# WF_AutoCar.net
KiCad netlist of a schematic drawn in Altium Designer
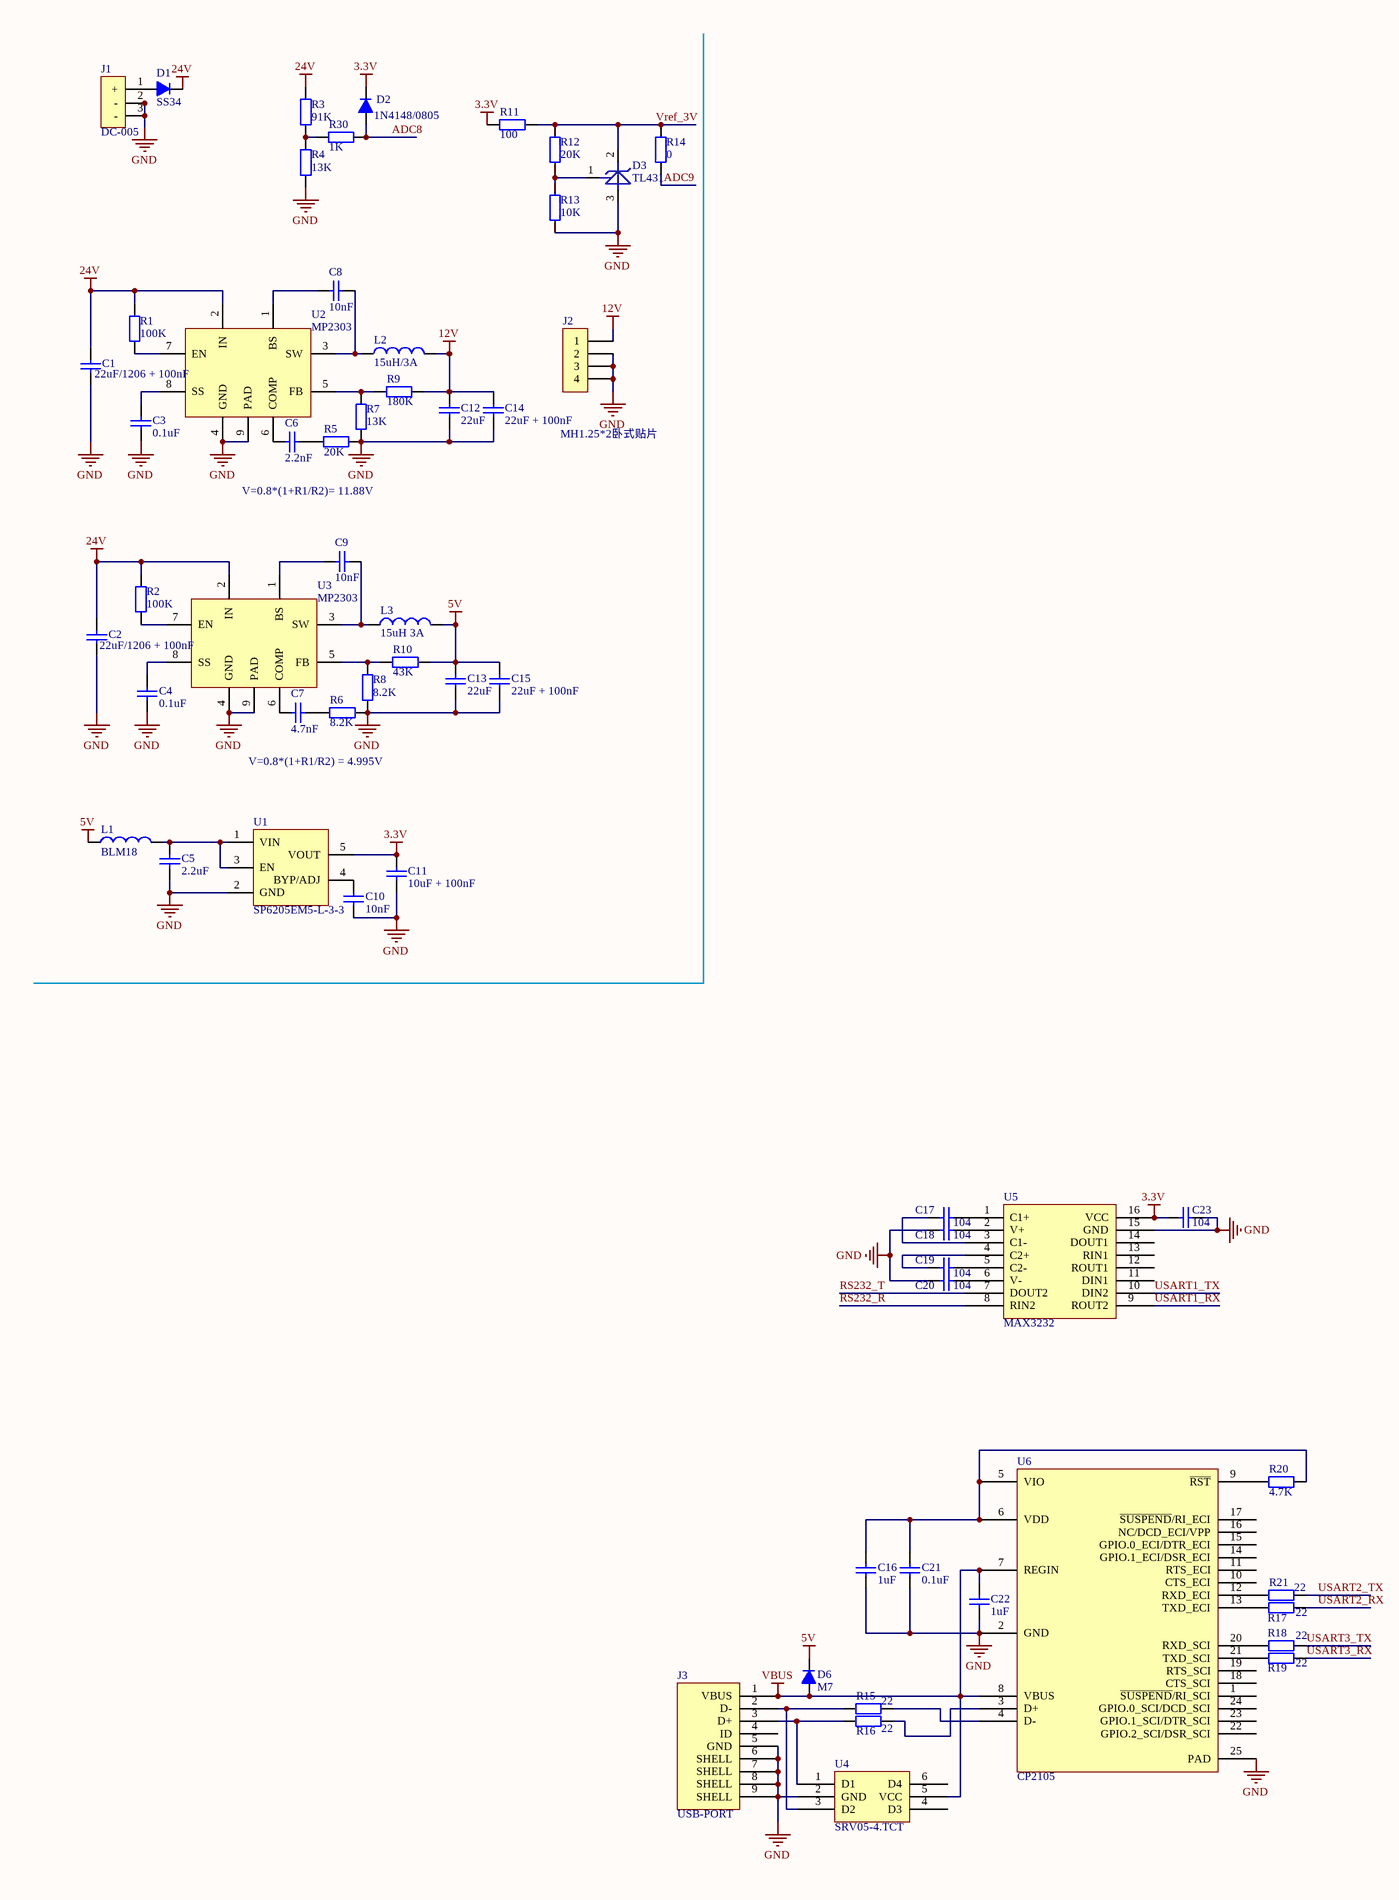
[diagram p0: WF_AutoCar.SchDoc, left]
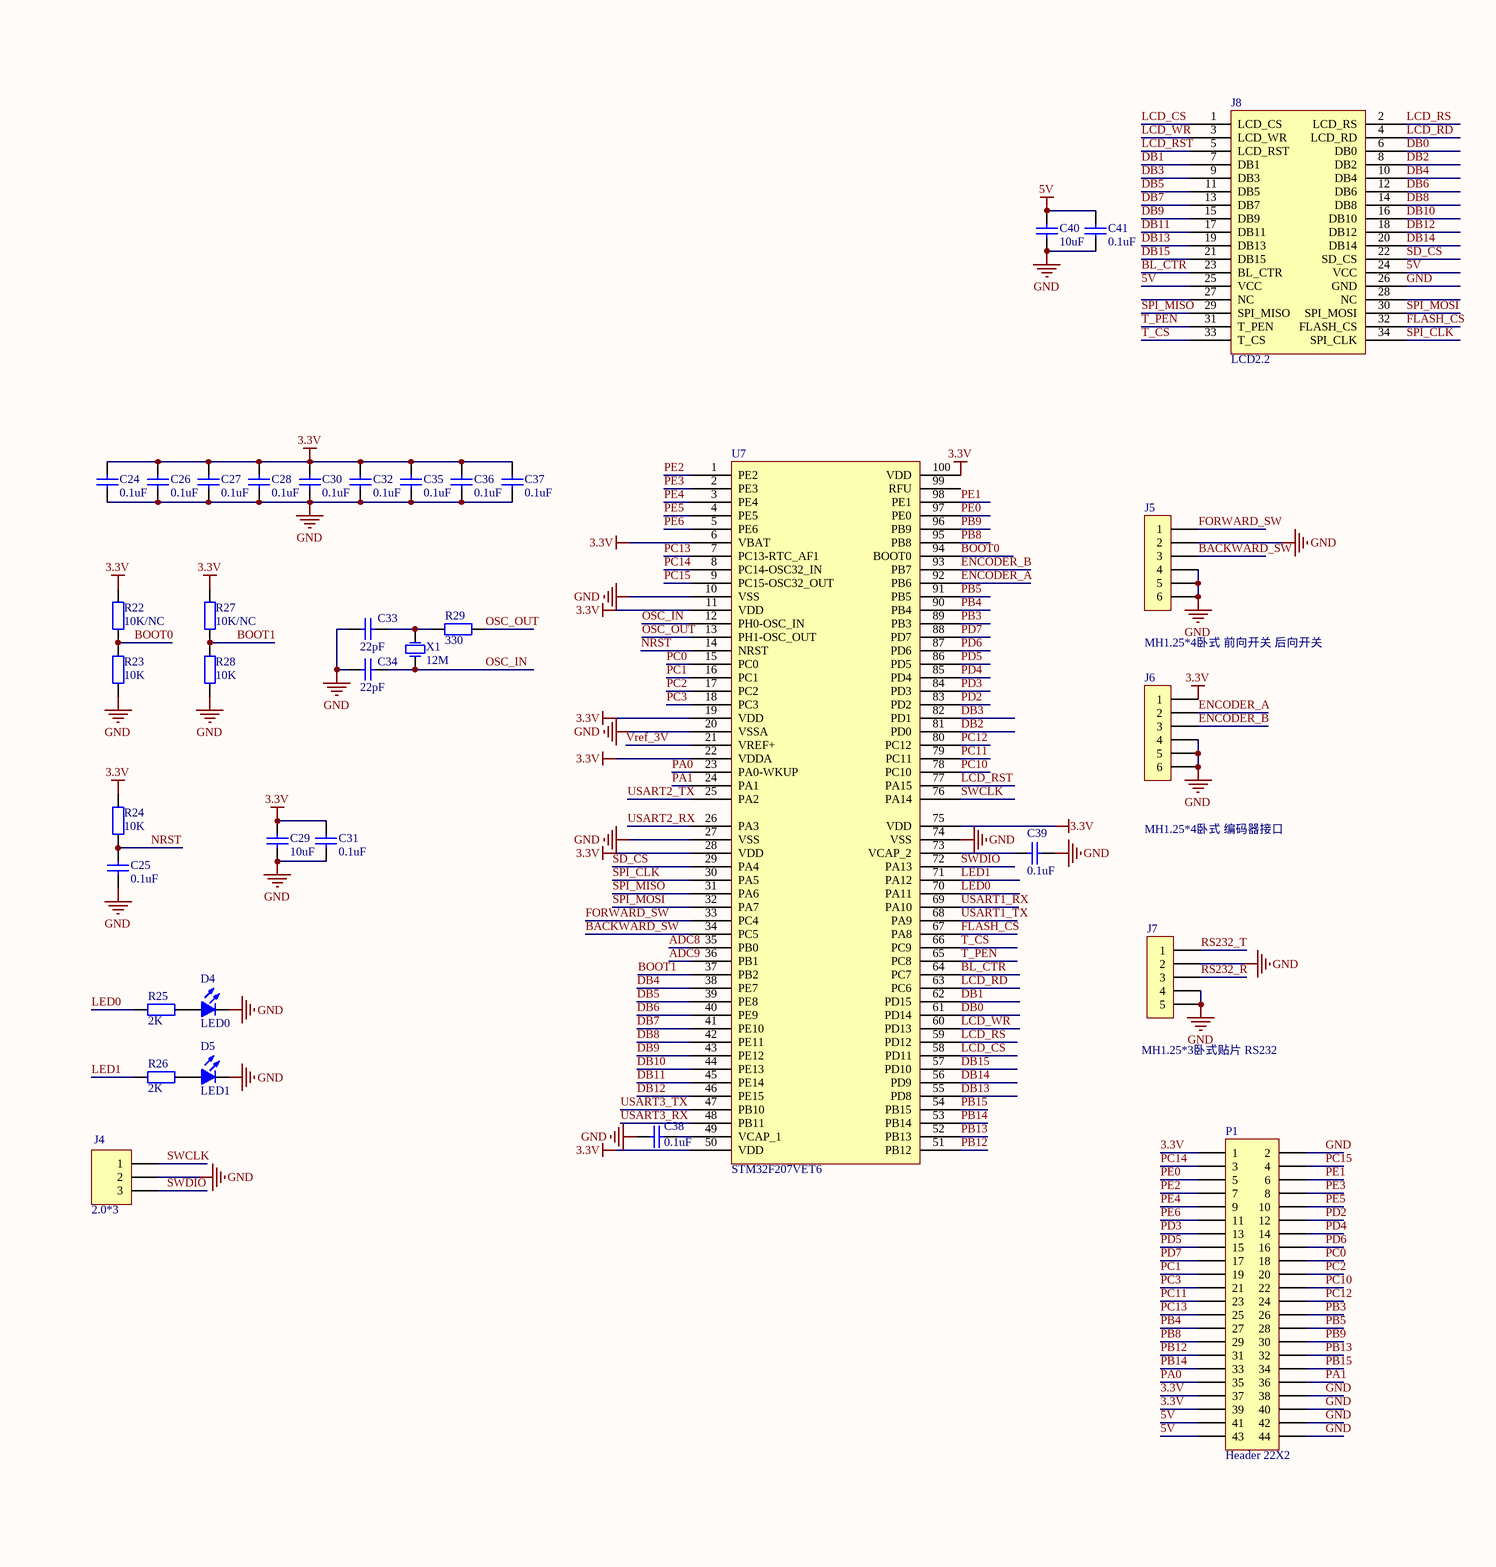
[diagram p1: WF_AutoCar.SchDoc, right]

(export (version "E")
  (design (tool "Eeschema 10.0.6"))
  (components
    (comp (ref "C1")
      (value "22uF/1206 + 100nF")
      (footprint "C1206")
      (description "Capacitor")
      (fields (field (name "Comment") "Cap1") (field (name "PUBLISHER") "Altium Limited"))
      (libsource (lib "weifengdq") (part "Cap1"))
    )
    (comp (ref "C2")
      (value "22uF/1206 + 100nF")
      (footprint "C1206")
      (description "Capacitor")
      (fields (field (name "Comment") "Cap1") (field (name "PUBLISHER") "Altium Limited"))
      (libsource (lib "weifengdq") (part "Cap1"))
    )
    (comp (ref "C3")
      (value "0.1uF")
      (footprint "C0402")
      (description "Capacitor")
      (fields (field (name "Comment") "Cap1") (field (name "PUBLISHER") "Altium Limited"))
      (libsource (lib "weifengdq") (part "Cap1"))
    )
    (comp (ref "C4")
      (value "0.1uF")
      (footprint "C0402")
      (description "Capacitor")
      (fields (field (name "Comment") "Cap1") (field (name "PUBLISHER") "Altium Limited"))
      (libsource (lib "weifengdq") (part "Cap1"))
    )
    (comp (ref "C5")
      (value "2.2uF")
      (footprint "CC0805")
      (description "Capacitor")
      (fields (field (name "Comment") "Cap1") (field (name "PUBLISHER") "Altium Limited"))
      (libsource (lib "weifengdq") (part "Cap1"))
    )
    (comp (ref "C6")
      (value "2.2nF")
      (footprint "C0402")
      (description "Capacitor")
      (fields (field (name "Comment") "Cap1") (field (name "PUBLISHER") "Altium Limited"))
      (libsource (lib "weifengdq") (part "Cap1"))
    )
    (comp (ref "C7")
      (value "4.7nF")
      (footprint "C0402")
      (description "Capacitor")
      (fields (field (name "Comment") "Cap1") (field (name "PUBLISHER") "Altium Limited"))
      (libsource (lib "weifengdq") (part "Cap1"))
    )
    (comp (ref "C8")
      (value "10nF")
      (footprint "C0402")
      (description "Capacitor")
      (fields (field (name "Comment") "Cap1") (field (name "PUBLISHER") "Altium Limited"))
      (libsource (lib "weifengdq") (part "Cap1"))
    )
    (comp (ref "C9")
      (value "10nF")
      (footprint "C0402")
      (description "Capacitor")
      (fields (field (name "Comment") "Cap1") (field (name "PUBLISHER") "Altium Limited"))
      (libsource (lib "weifengdq") (part "Cap1"))
    )
    (comp (ref "C10")
      (value "10nF")
      (footprint "C0402")
      (description "Capacitor")
      (fields (field (name "Comment") "Cap1") (field (name "PUBLISHER") "Altium Limited"))
      (libsource (lib "weifengdq") (part "Cap1"))
    )
    (comp (ref "C11")
      (value "10uF + 100nF")
      (footprint "CC0805")
      (description "Capacitor")
      (fields (field (name "Comment") "Cap1") (field (name "PUBLISHER") "Altium Limited"))
      (libsource (lib "weifengdq") (part "Cap1"))
    )
    (comp (ref "C12")
      (value "22uF")
      (footprint "CC0805")
      (description "Capacitor")
      (fields (field (name "Comment") "Cap1") (field (name "PUBLISHER") "Altium Limited"))
      (libsource (lib "weifengdq") (part "Cap1"))
    )
    (comp (ref "C13")
      (value "22uF")
      (footprint "CC0805")
      (description "Capacitor")
      (fields (field (name "Comment") "Cap1") (field (name "PUBLISHER") "Altium Limited"))
      (libsource (lib "weifengdq") (part "Cap1"))
    )
    (comp (ref "C14")
      (value "22uF + 100nF")
      (footprint "CC0805")
      (description "Capacitor")
      (fields (field (name "Comment") "Cap1") (field (name "PUBLISHER") "Altium Limited"))
      (libsource (lib "weifengdq") (part "Cap1"))
    )
    (comp (ref "C15")
      (value "22uF + 100nF")
      (footprint "CC0805")
      (description "Capacitor")
      (fields (field (name "Comment") "Cap1") (field (name "PUBLISHER") "Altium Limited"))
      (libsource (lib "weifengdq") (part "Cap1"))
    )
    (comp (ref "C16")
      (value "1uF")
      (footprint "C0402")
      (description "Capacitor")
      (fields (field (name "Comment") "Cap1") (field (name "PUBLISHER") "Altium Limited"))
      (libsource (lib "weifengdq") (part "Cap1"))
    )
    (comp (ref "C17")
      (value "104")
      (footprint "C0402")
      (description "Capacitor")
      (fields (field (name "Comment") "Cap1") (field (name "PUBLISHER") "Altium Limited"))
      (libsource (lib "weifengdq") (part "Cap1"))
    )
    (comp (ref "C18")
      (value "104")
      (footprint "C0402")
      (description "Capacitor")
      (fields (field (name "Comment") "Cap1") (field (name "PUBLISHER") "Altium Limited"))
      (libsource (lib "weifengdq") (part "Cap1"))
    )
    (comp (ref "C19")
      (value "104")
      (footprint "C0402")
      (description "Capacitor")
      (fields (field (name "Comment") "Cap1") (field (name "PUBLISHER") "Altium Limited"))
      (libsource (lib "weifengdq") (part "Cap1"))
    )
    (comp (ref "C20")
      (value "104")
      (footprint "C0402")
      (description "Capacitor")
      (fields (field (name "Comment") "Cap1") (field (name "PUBLISHER") "Altium Limited"))
      (libsource (lib "weifengdq") (part "Cap1"))
    )
    (comp (ref "C21")
      (value "0.1uF")
      (footprint "C0402")
      (description "Capacitor")
      (fields (field (name "Comment") "Cap1") (field (name "PUBLISHER") "Altium Limited"))
      (libsource (lib "weifengdq") (part "Cap1"))
    )
    (comp (ref "C22")
      (value "1uF")
      (footprint "C0402")
      (description "Capacitor")
      (fields (field (name "Comment") "Cap1") (field (name "PUBLISHER") "Altium Limited"))
      (libsource (lib "weifengdq") (part "Cap1"))
    )
    (comp (ref "C23")
      (value "104")
      (footprint "C0402")
      (description "Capacitor")
      (fields (field (name "Comment") "Cap1") (field (name "PUBLISHER") "Altium Limited"))
      (libsource (lib "weifengdq") (part "Cap1"))
    )
    (comp (ref "C24")
      (value "0.1uF")
      (footprint "C0402")
      (description "Capacitor")
      (fields (field (name "Comment") "Cap1") (field (name "PUBLISHER") "Altium Limited"))
      (libsource (lib "weifengdq") (part "Cap1"))
    )
    (comp (ref "C25")
      (value "0.1uF")
      (footprint "C0402")
      (description "Capacitor")
      (fields (field (name "Comment") "Cap1") (field (name "PUBLISHER") "Altium Limited"))
      (libsource (lib "weifengdq") (part "Cap1"))
    )
    (comp (ref "C26")
      (value "0.1uF")
      (footprint "C0402")
      (description "Capacitor")
      (fields (field (name "Comment") "Cap1") (field (name "PUBLISHER") "Altium Limited"))
      (libsource (lib "weifengdq") (part "Cap1"))
    )
    (comp (ref "C27")
      (value "0.1uF")
      (footprint "C0402")
      (description "Capacitor")
      (fields (field (name "Comment") "Cap1") (field (name "PUBLISHER") "Altium Limited"))
      (libsource (lib "weifengdq") (part "Cap1"))
    )
    (comp (ref "C28")
      (value "0.1uF")
      (footprint "C0402")
      (description "Capacitor")
      (fields (field (name "Comment") "Cap1") (field (name "PUBLISHER") "Altium Limited"))
      (libsource (lib "weifengdq") (part "Cap1"))
    )
    (comp (ref "C29")
      (value "10uF")
      (footprint "CC0805")
      (description "Capacitor")
      (fields (field (name "Comment") "Cap1") (field (name "PUBLISHER") "Altium Limited"))
      (libsource (lib "weifengdq") (part "Cap1"))
    )
    (comp (ref "C30")
      (value "0.1uF")
      (footprint "C0402")
      (description "Capacitor")
      (fields (field (name "Comment") "Cap1") (field (name "PUBLISHER") "Altium Limited"))
      (libsource (lib "weifengdq") (part "Cap1"))
    )
    (comp (ref "C31")
      (value "0.1uF")
      (footprint "C0402")
      (description "Capacitor")
      (fields (field (name "Comment") "Cap1") (field (name "PUBLISHER") "Altium Limited"))
      (libsource (lib "weifengdq") (part "Cap1"))
    )
    (comp (ref "C32")
      (value "0.1uF")
      (footprint "C0402")
      (description "Capacitor")
      (fields (field (name "Comment") "Cap1") (field (name "PUBLISHER") "Altium Limited"))
      (libsource (lib "weifengdq") (part "Cap1"))
    )
    (comp (ref "C33")
      (value "22pF")
      (footprint "C0402")
      (description "Capacitor")
      (fields (field (name "Comment") "Cap1") (field (name "PUBLISHER") "Altium Limited"))
      (libsource (lib "weifengdq") (part "Cap1"))
    )
    (comp (ref "C34")
      (value "22pF")
      (footprint "C0402")
      (description "Capacitor")
      (fields (field (name "Comment") "Cap1") (field (name "PUBLISHER") "Altium Limited"))
      (libsource (lib "weifengdq") (part "Cap1"))
    )
    (comp (ref "C35")
      (value "0.1uF")
      (footprint "C0402")
      (description "Capacitor")
      (fields (field (name "Comment") "Cap1") (field (name "PUBLISHER") "Altium Limited"))
      (libsource (lib "weifengdq") (part "Cap1"))
    )
    (comp (ref "C36")
      (value "0.1uF")
      (footprint "C0402")
      (description "Capacitor")
      (fields (field (name "Comment") "Cap1") (field (name "PUBLISHER") "Altium Limited"))
      (libsource (lib "weifengdq") (part "Cap1"))
    )
    (comp (ref "C37")
      (value "0.1uF")
      (footprint "C0402")
      (description "Capacitor")
      (fields (field (name "Comment") "Cap1") (field (name "PUBLISHER") "Altium Limited"))
      (libsource (lib "weifengdq") (part "Cap1"))
    )
    (comp (ref "C38")
      (value "0.1uF")
      (footprint "C0402")
      (description "Capacitor")
      (fields (field (name "Comment") "Cap1") (field (name "PUBLISHER") "Altium Limited"))
      (libsource (lib "weifengdq") (part "Cap1"))
    )
    (comp (ref "C39")
      (value "0.1uF")
      (footprint "C0402")
      (description "Capacitor")
      (fields (field (name "Comment") "Cap1") (field (name "PUBLISHER") "Altium Limited"))
      (libsource (lib "weifengdq") (part "Cap1"))
    )
    (comp (ref "C40")
      (value "10uF")
      (footprint "CC0805")
      (description "Capacitor")
      (fields (field (name "Comment") "Cap1") (field (name "PUBLISHER") "Altium Limited"))
      (libsource (lib "weifengdq") (part "Cap1"))
    )
    (comp (ref "C41")
      (value "0.1uF")
      (footprint "C0402")
      (description "Capacitor")
      (fields (field (name "Comment") "Cap1") (field (name "PUBLISHER") "Altium Limited"))
      (libsource (lib "weifengdq") (part "Cap1"))
    )
    (comp (ref "D1")
      (value "SS34")
      (footprint "LC-SMA(DO-214AC)_S2")
      (libsource (lib "weifengdq") (part "Diode1"))
    )
    (comp (ref "D2")
      (value "1N4148/0805")
      (footprint "Diode-0805")
      (libsource (lib "weifengdq") (part "Diode1"))
    )
    (comp (ref "D3") (value "TL431") (footprint "SOT-23") (libsource (lib "weifengdq") (part "TL431-SOT23")))
    (comp (ref "D4")
      (value "LED0")
      (footprint "DIODE-12")
      (description "Typical INFRARED GaAs LED")
      (fields (field (name "PUBLISHER") "Altium Limited"))
      (libsource (lib "weifengdq") (part "LED1"))
    )
    (comp (ref "D5")
      (value "LED1")
      (footprint "DIODE-12")
      (description "Typical INFRARED GaAs LED")
      (fields (field (name "PUBLISHER") "Altium Limited"))
      (libsource (lib "weifengdq") (part "LED1"))
    )
    (comp (ref "D6")
      (value "M7")
      (footprint "LC-SMA(DO-214AC)_S2")
      (libsource (lib "weifengdq") (part "Diode1"))
    )
    (comp (ref "J1") (value "DC-005") (footprint "DC10B") (libsource (lib "weifengdq") (part "DC-005")))
    (comp (ref "J2")
      (value "MH1.25*2卧式贴片")
      (footprint "MH1.25*2立式表贴")
      (libsource (lib "weifengdq") (part "MH1.25*2卧式贴片"))
    )
    (comp (ref "J3")
      (value "USB-PORT")
      (footprint "USB/SM0.8-6H5")
      (libsource (lib "weifengdq") (part "USB-PORT"))
    )
    (comp (ref "J4")
      (value "2.0*3")
      (footprint "Con3_2.0")
      (description "Header, 3-Pin")
      (fields (field (name "PUBLISHER") "Altium Limited"))
      (libsource (lib "weifengdq") (part "Con3_2.0"))
    )
    (comp (ref "J5")
      (value "MH1.25*4卧式 前向开关 后向开关")
      (footprint "MH1.25*4立式表贴")
      (libsource (lib "weifengdq") (part "MH1.25*4立式贴片"))
    )
    (comp (ref "J6")
      (value "MH1.25*4卧式 编码器接口")
      (footprint "MH1.25*4立式表贴")
      (libsource (lib "weifengdq") (part "MH1.25*4立式贴片"))
    )
    (comp (ref "J7")
      (value "MH1.25*3卧式贴片 RS232")
      (footprint "MH1.25*3立式表贴")
      (libsource (lib "weifengdq") (part "MH1.25*3卧式贴片"))
    )
    (comp (ref "J8")
      (value "LCD2.2")
      (footprint "2.2TFT_ILI9325")
      (libsource (lib "weifengdq") (part "2.2 LCD ILI9325"))
    )
    (comp (ref "L1") (value "BLM18") (footprint "CC0805") (libsource (lib "weifengdq") (part "BLM18")))
    (comp (ref "L2")
      (value "15uH/3A")
      (footprint "0630")
      (description "Inductor")
      (fields (field (name "PUBLISHER") "Altium Limited"))
      (libsource (lib "weifengdq") (part "Inductor"))
    )
    (comp (ref "L3")
      (value "15uH 3A")
      (footprint "0630")
      (description "Inductor")
      (fields (field (name "PUBLISHER") "Altium Limited"))
      (libsource (lib "weifengdq") (part "Inductor"))
    )
    (comp (ref "P1")
      (value "Header 22X2")
      (footprint "HDR2X22")
      (description "Header, 22-Pin, Dual row")
      (fields (field (name "PUBLISHER") "Altium Limited"))
      (libsource (lib "Miscellaneous Connectors") (part "Header 22X2"))
    )
    (comp (ref "R1")
      (value "100K")
      (footprint "C0402")
      (description "Resistor")
      (fields (field (name "Comment") "Res1") (field (name "PUBLISHER") "Altium Limited"))
      (libsource (lib "weifengdq") (part "Res1"))
    )
    (comp (ref "R2")
      (value "100K")
      (footprint "C0402")
      (description "Resistor")
      (fields (field (name "Comment") "Res1") (field (name "PUBLISHER") "Altium Limited"))
      (libsource (lib "weifengdq") (part "Res1"))
    )
    (comp (ref "R3")
      (value "91K")
      (footprint "C0402")
      (description "Resistor")
      (fields (field (name "Comment") "Res1") (field (name "PUBLISHER") "Altium Limited"))
      (libsource (lib "weifengdq") (part "Res1"))
    )
    (comp (ref "R4")
      (value "13K")
      (footprint "C0402")
      (description "Resistor")
      (fields (field (name "Comment") "Res1") (field (name "PUBLISHER") "Altium Limited"))
      (libsource (lib "weifengdq") (part "Res1"))
    )
    (comp (ref "R5")
      (value "20K")
      (footprint "C0402")
      (description "Resistor")
      (fields (field (name "Comment") "Res1") (field (name "PUBLISHER") "Altium Limited"))
      (libsource (lib "") (part "Res1_1"))
    )
    (comp (ref "R6")
      (value "8.2K")
      (footprint "C0402")
      (description "Resistor")
      (fields (field (name "Comment") "Res1") (field (name "PUBLISHER") "Altium Limited"))
      (libsource (lib "") (part "Res1_1"))
    )
    (comp (ref "R7")
      (value "13K")
      (footprint "C0402")
      (description "Resistor")
      (fields (field (name "Comment") "Res1") (field (name "PUBLISHER") "Altium Limited"))
      (libsource (lib "weifengdq") (part "Res1"))
    )
    (comp (ref "R8")
      (value "8.2K")
      (footprint "C0402")
      (description "Resistor")
      (fields (field (name "Comment") "Res1") (field (name "PUBLISHER") "Altium Limited"))
      (libsource (lib "weifengdq") (part "Res1"))
    )
    (comp (ref "R9")
      (value "180K")
      (footprint "C0402")
      (description "Resistor")
      (fields (field (name "Comment") "Res1") (field (name "PUBLISHER") "Altium Limited"))
      (libsource (lib "") (part "Res1_1"))
    )
    (comp (ref "R10")
      (value "43K")
      (footprint "C0402")
      (description "Resistor")
      (fields (field (name "Comment") "Res1") (field (name "PUBLISHER") "Altium Limited"))
      (libsource (lib "") (part "Res1_1"))
    )
    (comp (ref "R11")
      (value "100")
      (footprint "C0402")
      (description "Resistor")
      (fields (field (name "Comment") "Res1") (field (name "PUBLISHER") "Altium Limited"))
      (libsource (lib "") (part "Res1_2"))
    )
    (comp (ref "R12")
      (value "20K")
      (footprint "C0402")
      (description "Resistor")
      (fields (field (name "Comment") "Res1") (field (name "PUBLISHER") "Altium Limited"))
      (libsource (lib "") (part "Res1_3"))
    )
    (comp (ref "R13")
      (value "10K")
      (footprint "C0402")
      (description "Resistor")
      (fields (field (name "Comment") "Res1") (field (name "PUBLISHER") "Altium Limited"))
      (libsource (lib "") (part "Res1_3"))
    )
    (comp (ref "R14")
      (value "0")
      (footprint "C0402")
      (description "Resistor")
      (fields (field (name "Comment") "Res1") (field (name "PUBLISHER") "Altium Limited"))
      (libsource (lib "weifengdq") (part "Res1"))
    )
    (comp (ref "R15")
      (value "22")
      (footprint "C0402")
      (description "Resistor")
      (fields (field (name "Comment") "Res1") (field (name "PUBLISHER") "Altium Limited"))
      (libsource (lib "") (part "Res1_1"))
    )
    (comp (ref "R16")
      (value "22")
      (footprint "C0402")
      (description "Resistor")
      (fields (field (name "Comment") "Res1") (field (name "PUBLISHER") "Altium Limited"))
      (libsource (lib "") (part "Res1_1"))
    )
    (comp (ref "R17")
      (value "22")
      (footprint "C0402")
      (description "Resistor")
      (fields (field (name "Comment") "Res1") (field (name "PUBLISHER") "Altium Limited"))
      (libsource (lib "") (part "Res1_1"))
    )
    (comp (ref "R18")
      (value "22")
      (footprint "C0402")
      (description "Resistor")
      (fields (field (name "Comment") "Res1") (field (name "PUBLISHER") "Altium Limited"))
      (libsource (lib "") (part "Res1_1"))
    )
    (comp (ref "R19")
      (value "22")
      (footprint "C0402")
      (description "Resistor")
      (fields (field (name "Comment") "Res1") (field (name "PUBLISHER") "Altium Limited"))
      (libsource (lib "") (part "Res1_1"))
    )
    (comp (ref "R20")
      (value "4.7K")
      (footprint "C0402")
      (description "Resistor")
      (fields (field (name "Comment") "Res1") (field (name "PUBLISHER") "Altium Limited"))
      (libsource (lib "") (part "Res1_1"))
    )
    (comp (ref "R21")
      (value "22")
      (footprint "C0402")
      (description "Resistor")
      (fields (field (name "Comment") "Res1") (field (name "PUBLISHER") "Altium Limited"))
      (libsource (lib "") (part "Res1_1"))
    )
    (comp (ref "R22")
      (value "10K/NC")
      (footprint "C0402")
      (description "Resistor")
      (fields (field (name "Comment") "Res1") (field (name "PUBLISHER") "Altium Limited"))
      (libsource (lib "weifengdq") (part "Res1"))
    )
    (comp (ref "R23")
      (value "10K")
      (footprint "C0402")
      (description "Resistor")
      (fields (field (name "Comment") "Res1") (field (name "PUBLISHER") "Altium Limited"))
      (libsource (lib "weifengdq") (part "Res1"))
    )
    (comp (ref "R24")
      (value "10K")
      (footprint "C0402")
      (description "Resistor")
      (fields (field (name "Comment") "Res1") (field (name "PUBLISHER") "Altium Limited"))
      (libsource (lib "") (part "Res1_3"))
    )
    (comp (ref "R25")
      (value "2K")
      (footprint "C0402")
      (description "Resistor")
      (fields (field (name "Comment") "Res1") (field (name "PUBLISHER") "Altium Limited"))
      (libsource (lib "") (part "Res1_1"))
    )
    (comp (ref "R26")
      (value "2K")
      (footprint "C0402")
      (description "Resistor")
      (fields (field (name "Comment") "Res1") (field (name "PUBLISHER") "Altium Limited"))
      (libsource (lib "") (part "Res1_1"))
    )
    (comp (ref "R27")
      (value "10K/NC")
      (footprint "C0402")
      (description "Resistor")
      (fields (field (name "Comment") "Res1") (field (name "PUBLISHER") "Altium Limited"))
      (libsource (lib "weifengdq") (part "Res1"))
    )
    (comp (ref "R28")
      (value "10K")
      (footprint "C0402")
      (description "Resistor")
      (fields (field (name "Comment") "Res1") (field (name "PUBLISHER") "Altium Limited"))
      (libsource (lib "weifengdq") (part "Res1"))
    )
    (comp (ref "R29")
      (value "330")
      (footprint "C0402")
      (description "Resistor")
      (fields (field (name "Comment") "Res1") (field (name "PUBLISHER") "Altium Limited"))
      (libsource (lib "") (part "Res1_2"))
    )
    (comp (ref "R30")
      (value "1K")
      (footprint "C0402")
      (description "Resistor")
      (fields (field (name "Comment") "Res1") (field (name "PUBLISHER") "Altium Limited"))
      (libsource (lib "") (part "Res1_1"))
    )
    (comp (ref "U1")
      (value "SP6205EM5-L-3-3")
      (footprint "LC-SOT-23-5")
      (libsource (lib "weifengdq") (part "SP6205EM5-L-3-3"))
    )
    (comp (ref "U2")
      (value "MP2303")
      (footprint "LC-SOIC-8_150mil")
      (libsource (lib "weifengdq") (part "MP2307"))
    )
    (comp (ref "U3")
      (value "MP2303")
      (footprint "LC-SOIC-8_150mil")
      (libsource (lib "weifengdq") (part "MP2307"))
    )
    (comp (ref "U4")
      (value "SRV05-4.TCT")
      (footprint "LC-SOT-23-6")
      (libsource (lib "weifengdq") (part "SRV05-4.TCT"))
    )
    (comp (ref "U5") (value "MAX3232") (footprint "SOP16M") (libsource (lib "weifengdq") (part "MAX3232")))
    (comp (ref "U6") (value "CP2105") (footprint "QFN-24") (libsource (lib "weifengdq") (part "CP2105")))
    (comp (ref "U7")
      (value "STM32F207VET6")
      (footprint "LC-LQFP-100_14x14x05P")
      (libsource (lib "weifengdq") (part "STM32F207VET6"))
    )
    (comp (ref "X1")
      (value "12M")
      (footprint "XTAL-3225")
      (description "Crystal Oscillator")
      (fields (field (name "PUBLISHER") "Altium Limited"))
      (libsource (lib "weifengdq") (part "XTAL_1"))
    )
  )
  (nets
    (net (code "1") (name "/ADC8") (class "Default")
      (node (ref "D2") (pin "1") (pinfunction "A_1") (pintype "passive"))
      (node (ref "R30") (pin "2") (pinfunction "2_2") (pintype "passive"))
      (node (ref "U7") (pin "35") (pinfunction "PB0_35") (pintype "passive"))
    )
    (net (code "2") (name "/ADC9") (class "Default")
      (node (ref "R14") (pin "1") (pinfunction "1_1") (pintype "passive"))
      (node (ref "U7") (pin "36") (pinfunction "PB1_36") (pintype "passive"))
    )
    (net (code "3") (name "/BACKWARD_SW") (class "Default")
      (node (ref "J5") (pin "3") (pinfunction "3_3") (pintype "passive"))
      (node (ref "U7") (pin "34") (pinfunction "PC5_34") (pintype "passive"))
    )
    (net (code "4") (name "/BL_CTR") (class "Default")
      (node (ref "J8") (pin "23") (pinfunction "BL_CTR_23") (pintype "passive"))
      (node (ref "U7") (pin "64") (pinfunction "PC7_64") (pintype "passive"))
    )
    (net (code "5") (name "/BOOT0") (class "Default")
      (node (ref "R22") (pin "1") (pinfunction "1_1") (pintype "passive"))
      (node (ref "R23") (pin "2") (pinfunction "2_2") (pintype "passive"))
      (node (ref "U7") (pin "94") (pinfunction "BOOT0_94") (pintype "passive"))
    )
    (net (code "6") (name "/BOOT1") (class "Default")
      (node (ref "R27") (pin "1") (pinfunction "1_1") (pintype "passive"))
      (node (ref "R28") (pin "2") (pinfunction "2_2") (pintype "passive"))
      (node (ref "U7") (pin "37") (pinfunction "PB2_37") (pintype "passive"))
    )
    (net (code "7") (name "/DB0") (class "Default")
      (node (ref "J8") (pin "6") (pinfunction "DB0_6") (pintype "passive"))
      (node (ref "U7") (pin "61") (pinfunction "PD14_61") (pintype "passive"))
    )
    (net (code "8") (name "/DB1") (class "Default")
      (node (ref "J8") (pin "7") (pinfunction "DB1_7") (pintype "passive"))
      (node (ref "U7") (pin "62") (pinfunction "PD15_62") (pintype "passive"))
    )
    (net (code "9") (name "/DB2") (class "Default")
      (node (ref "J8") (pin "8") (pinfunction "DB2_8") (pintype "passive"))
      (node (ref "U7") (pin "81") (pinfunction "PD0_81") (pintype "passive"))
    )
    (net (code "10") (name "/DB3") (class "Default")
      (node (ref "J8") (pin "9") (pinfunction "DB3_9") (pintype "passive"))
      (node (ref "U7") (pin "82") (pinfunction "PD1_82") (pintype "passive"))
    )
    (net (code "11") (name "/DB4") (class "Default")
      (node (ref "J8") (pin "10") (pinfunction "DB4_10") (pintype "passive"))
      (node (ref "U7") (pin "38") (pinfunction "PE7_38") (pintype "passive"))
    )
    (net (code "12") (name "/DB5") (class "Default")
      (node (ref "J8") (pin "11") (pinfunction "DB5_11") (pintype "passive"))
      (node (ref "U7") (pin "39") (pinfunction "PE8_39") (pintype "passive"))
    )
    (net (code "13") (name "/DB6") (class "Default")
      (node (ref "J8") (pin "12") (pinfunction "DB6_12") (pintype "passive"))
      (node (ref "U7") (pin "40") (pinfunction "PE9_40") (pintype "passive"))
    )
    (net (code "14") (name "/DB7") (class "Default")
      (node (ref "J8") (pin "13") (pinfunction "DB7_13") (pintype "passive"))
      (node (ref "U7") (pin "41") (pinfunction "PE10_41") (pintype "passive"))
    )
    (net (code "15") (name "/DB8") (class "Default")
      (node (ref "J8") (pin "14") (pinfunction "DB8_14") (pintype "passive"))
      (node (ref "U7") (pin "42") (pinfunction "PE11_42") (pintype "passive"))
    )
    (net (code "16") (name "/DB9") (class "Default")
      (node (ref "J8") (pin "15") (pinfunction "DB9_15") (pintype "passive"))
      (node (ref "U7") (pin "43") (pinfunction "PE12_43") (pintype "passive"))
    )
    (net (code "17") (name "/DB10") (class "Default")
      (node (ref "J8") (pin "16") (pinfunction "DB10_16") (pintype "passive"))
      (node (ref "U7") (pin "44") (pinfunction "PE13_44") (pintype "passive"))
    )
    (net (code "18") (name "/DB11") (class "Default")
      (node (ref "J8") (pin "17") (pinfunction "DB11_17") (pintype "passive"))
      (node (ref "U7") (pin "45") (pinfunction "PE14_45") (pintype "passive"))
    )
    (net (code "19") (name "/DB12") (class "Default")
      (node (ref "J8") (pin "18") (pinfunction "DB12_18") (pintype "passive"))
      (node (ref "U7") (pin "46") (pinfunction "PE15_46") (pintype "passive"))
    )
    (net (code "20") (name "/DB13") (class "Default")
      (node (ref "J8") (pin "19") (pinfunction "DB13_19") (pintype "passive"))
      (node (ref "U7") (pin "55") (pinfunction "PD8_55") (pintype "passive"))
    )
    (net (code "21") (name "/DB14") (class "Default")
      (node (ref "J8") (pin "20") (pinfunction "DB14_20") (pintype "passive"))
      (node (ref "U7") (pin "56") (pinfunction "PD9_56") (pintype "passive"))
    )
    (net (code "22") (name "/DB15") (class "Default")
      (node (ref "J8") (pin "21") (pinfunction "DB15_21") (pintype "passive"))
      (node (ref "U7") (pin "57") (pinfunction "PD10_57") (pintype "passive"))
    )
    (net (code "23") (name "/ENCODER_A") (class "Default")
      (node (ref "J6") (pin "2") (pinfunction "2_2") (pintype "passive"))
      (node (ref "U7") (pin "92") (pinfunction "PB6_92") (pintype "passive"))
    )
    (net (code "24") (name "/ENCODER_B") (class "Default")
      (node (ref "J6") (pin "3") (pinfunction "3_3") (pintype "passive"))
      (node (ref "U7") (pin "93") (pinfunction "PB7_93") (pintype "passive"))
    )
    (net (code "25") (name "/FLASH_CS") (class "Default")
      (node (ref "J8") (pin "32") (pinfunction "FLASH_CS_32") (pintype "passive"))
      (node (ref "U7") (pin "67") (pinfunction "PA8_67") (pintype "passive"))
    )
    (net (code "26") (name "/FORWARD_SW") (class "Default")
      (node (ref "J5") (pin "1") (pinfunction "1_1") (pintype "passive"))
      (node (ref "U7") (pin "33") (pinfunction "PC4_33") (pintype "passive"))
    )
    (net (code "27") (name "/LCD_CS") (class "Default")
      (node (ref "J8") (pin "1") (pinfunction "LCD_CS_1") (pintype "passive"))
      (node (ref "U7") (pin "58") (pinfunction "PD11_58") (pintype "passive"))
    )
    (net (code "28") (name "/LCD_RD") (class "Default")
      (node (ref "J8") (pin "4") (pinfunction "LCD_RD_4") (pintype "passive"))
      (node (ref "U7") (pin "63") (pinfunction "PC6_63") (pintype "passive"))
    )
    (net (code "29") (name "/LCD_RS") (class "Default")
      (node (ref "J8") (pin "2") (pinfunction "LCD_RS_2") (pintype "passive"))
      (node (ref "U7") (pin "59") (pinfunction "PD12_59") (pintype "passive"))
    )
    (net (code "30") (name "/LCD_RST") (class "Default")
      (node (ref "J8") (pin "5") (pinfunction "LCD_RST_5") (pintype "passive"))
      (node (ref "U7") (pin "77") (pinfunction "PA15_77") (pintype "passive"))
    )
    (net (code "31") (name "/LCD_WR") (class "Default")
      (node (ref "J8") (pin "3") (pinfunction "LCD_WR_3") (pintype "passive"))
      (node (ref "U7") (pin "60") (pinfunction "PD13_60") (pintype "passive"))
    )
    (net (code "32") (name "/LED0") (class "Default")
      (node (ref "R25") (pin "1") (pinfunction "1_1") (pintype "passive"))
      (node (ref "U7") (pin "70") (pinfunction "PA11_70") (pintype "passive"))
    )
    (net (code "33") (name "/LED1") (class "Default")
      (node (ref "R26") (pin "1") (pinfunction "1_1") (pintype "passive"))
      (node (ref "U7") (pin "71") (pinfunction "PA12_71") (pintype "passive"))
    )
    (net (code "34") (name "/NRST") (class "Default")
      (node (ref "C25") (pin "2") (pinfunction "2_2") (pintype "passive"))
      (node (ref "R24") (pin "2") (pinfunction "2_2") (pintype "passive"))
      (node (ref "U7") (pin "14") (pinfunction "NRST_14") (pintype "passive"))
    )
    (net (code "35") (name "/OSC_IN") (class "Default")
      (node (ref "C34") (pin "1") (pinfunction "1_1") (pintype "passive"))
      (node (ref "U7") (pin "12") (pinfunction "PH0-OSC_IN_12") (pintype "passive"))
      (node (ref "X1") (pin "2") (pinfunction "OSC2_2") (pintype "passive"))
    )
    (net (code "36") (name "/OSC_OUT") (class "Default")
      (node (ref "R29") (pin "1") (pinfunction "1_1") (pintype "passive"))
      (node (ref "U7") (pin "13") (pinfunction "PH1-OSC_OUT_13") (pintype "passive"))
    )
    (net (code "37") (name "/PA0") (class "Default")
      (node (ref "P1") (pin "35") (pinfunction "35_35") (pintype "passive"))
      (node (ref "U7") (pin "23") (pinfunction "PA0-WKUP_23") (pintype "passive"))
    )
    (net (code "38") (name "/PA1") (class "Default")
      (node (ref "P1") (pin "36") (pinfunction "36_36") (pintype "passive"))
      (node (ref "U7") (pin "24") (pinfunction "PA1_24") (pintype "passive"))
    )
    (net (code "39") (name "/PB3") (class "Default")
      (node (ref "P1") (pin "26") (pinfunction "26_26") (pintype "passive"))
      (node (ref "U7") (pin "89") (pinfunction "PB3_89") (pintype "passive"))
    )
    (net (code "40") (name "/PB4") (class "Default")
      (node (ref "P1") (pin "27") (pinfunction "27_27") (pintype "passive"))
      (node (ref "U7") (pin "90") (pinfunction "PB4_90") (pintype "passive"))
    )
    (net (code "41") (name "/PB5") (class "Default")
      (node (ref "P1") (pin "28") (pinfunction "28_28") (pintype "passive"))
      (node (ref "U7") (pin "91") (pinfunction "PB5_91") (pintype "passive"))
    )
    (net (code "42") (name "/PB8") (class "Default")
      (node (ref "P1") (pin "29") (pinfunction "29_29") (pintype "passive"))
      (node (ref "U7") (pin "95") (pinfunction "PB8_95") (pintype "passive"))
    )
    (net (code "43") (name "/PB9") (class "Default")
      (node (ref "P1") (pin "30") (pinfunction "30_30") (pintype "passive"))
      (node (ref "U7") (pin "96") (pinfunction "PB9_96") (pintype "passive"))
    )
    (net (code "44") (name "/PB12") (class "Default")
      (node (ref "P1") (pin "31") (pinfunction "31_31") (pintype "passive"))
      (node (ref "U7") (pin "51") (pinfunction "PB12_51") (pintype "passive"))
    )
    (net (code "45") (name "/PB13") (class "Default")
      (node (ref "P1") (pin "32") (pinfunction "32_32") (pintype "passive"))
      (node (ref "U7") (pin "52") (pinfunction "PB13_52") (pintype "passive"))
    )
    (net (code "46") (name "/PB14") (class "Default")
      (node (ref "P1") (pin "33") (pinfunction "33_33") (pintype "passive"))
      (node (ref "U7") (pin "53") (pinfunction "PB14_53") (pintype "passive"))
    )
    (net (code "47") (name "/PB15") (class "Default")
      (node (ref "P1") (pin "34") (pinfunction "34_34") (pintype "passive"))
      (node (ref "U7") (pin "54") (pinfunction "PB15_54") (pintype "passive"))
    )
    (net (code "48") (name "/PC0") (class "Default")
      (node (ref "P1") (pin "18") (pinfunction "18_18") (pintype "passive"))
      (node (ref "U7") (pin "15") (pinfunction "PC0_15") (pintype "passive"))
    )
    (net (code "49") (name "/PC1") (class "Default")
      (node (ref "P1") (pin "19") (pinfunction "19_19") (pintype "passive"))
      (node (ref "U7") (pin "16") (pinfunction "PC1_16") (pintype "passive"))
    )
    (net (code "50") (name "/PC2") (class "Default")
      (node (ref "P1") (pin "20") (pinfunction "20_20") (pintype "passive"))
      (node (ref "U7") (pin "17") (pinfunction "PC2_17") (pintype "passive"))
    )
    (net (code "51") (name "/PC3") (class "Default")
      (node (ref "P1") (pin "21") (pinfunction "21_21") (pintype "passive"))
      (node (ref "U7") (pin "18") (pinfunction "PC3_18") (pintype "passive"))
    )
    (net (code "52") (name "/PC10") (class "Default")
      (node (ref "P1") (pin "22") (pinfunction "22_22") (pintype "passive"))
      (node (ref "U7") (pin "78") (pinfunction "PC10_78") (pintype "passive"))
    )
    (net (code "53") (name "/PC11") (class "Default")
      (node (ref "P1") (pin "23") (pinfunction "23_23") (pintype "passive"))
      (node (ref "U7") (pin "79") (pinfunction "PC11_79") (pintype "passive"))
    )
    (net (code "54") (name "/PC12") (class "Default")
      (node (ref "P1") (pin "24") (pinfunction "24_24") (pintype "passive"))
      (node (ref "U7") (pin "80") (pinfunction "PC12_80") (pintype "passive"))
    )
    (net (code "55") (name "/PC13") (class "Default")
      (node (ref "P1") (pin "25") (pinfunction "25_25") (pintype "passive"))
      (node (ref "U7") (pin "7") (pinfunction "PC13-RTC_AF1_7") (pintype "passive"))
    )
    (net (code "56") (name "/PC14") (class "Default")
      (node (ref "P1") (pin "3") (pinfunction "3_3") (pintype "passive"))
      (node (ref "U7") (pin "8") (pinfunction "PC14-OSC32_IN_8") (pintype "passive"))
    )
    (net (code "57") (name "/PC15") (class "Default")
      (node (ref "P1") (pin "4") (pinfunction "4_4") (pintype "passive"))
      (node (ref "U7") (pin "9") (pinfunction "PC15-OSC32_OUT_9") (pintype "passive"))
    )
    (net (code "58") (name "/PD2") (class "Default")
      (node (ref "P1") (pin "12") (pinfunction "12_12") (pintype "passive"))
      (node (ref "U7") (pin "83") (pinfunction "PD2_83") (pintype "passive"))
    )
    (net (code "59") (name "/PD3") (class "Default")
      (node (ref "P1") (pin "13") (pinfunction "13_13") (pintype "passive"))
      (node (ref "U7") (pin "84") (pinfunction "PD3_84") (pintype "passive"))
    )
    (net (code "60") (name "/PD4") (class "Default")
      (node (ref "P1") (pin "14") (pinfunction "14_14") (pintype "passive"))
      (node (ref "U7") (pin "85") (pinfunction "PD4_85") (pintype "passive"))
    )
    (net (code "61") (name "/PD5") (class "Default")
      (node (ref "P1") (pin "15") (pinfunction "15_15") (pintype "passive"))
      (node (ref "U7") (pin "86") (pinfunction "PD5_86") (pintype "passive"))
    )
    (net (code "62") (name "/PD6") (class "Default")
      (node (ref "P1") (pin "16") (pinfunction "16_16") (pintype "passive"))
      (node (ref "U7") (pin "87") (pinfunction "PD6_87") (pintype "passive"))
    )
    (net (code "63") (name "/PD7") (class "Default")
      (node (ref "P1") (pin "17") (pinfunction "17_17") (pintype "passive"))
      (node (ref "U7") (pin "88") (pinfunction "PD7_88") (pintype "passive"))
    )
    (net (code "64") (name "/PE0") (class "Default")
      (node (ref "P1") (pin "5") (pinfunction "5_5") (pintype "passive"))
      (node (ref "U7") (pin "97") (pinfunction "PE0_97") (pintype "passive"))
    )
    (net (code "65") (name "/PE1") (class "Default")
      (node (ref "P1") (pin "6") (pinfunction "6_6") (pintype "passive"))
      (node (ref "U7") (pin "98") (pinfunction "PE1_98") (pintype "passive"))
    )
    (net (code "66") (name "/PE2") (class "Default")
      (node (ref "P1") (pin "7") (pinfunction "7_7") (pintype "passive"))
      (node (ref "U7") (pin "1") (pinfunction "PE2_1") (pintype "passive"))
    )
    (net (code "67") (name "/PE3") (class "Default")
      (node (ref "P1") (pin "8") (pinfunction "8_8") (pintype "passive"))
      (node (ref "U7") (pin "2") (pinfunction "PE3_2") (pintype "passive"))
    )
    (net (code "68") (name "/PE4") (class "Default")
      (node (ref "P1") (pin "9") (pinfunction "9_9") (pintype "passive"))
      (node (ref "U7") (pin "3") (pinfunction "PE4_3") (pintype "passive"))
    )
    (net (code "69") (name "/PE5") (class "Default")
      (node (ref "P1") (pin "10") (pinfunction "10_10") (pintype "passive"))
      (node (ref "U7") (pin "4") (pinfunction "PE5_4") (pintype "passive"))
    )
    (net (code "70") (name "/PE6") (class "Default")
      (node (ref "P1") (pin "11") (pinfunction "11_11") (pintype "passive"))
      (node (ref "U7") (pin "5") (pinfunction "PE6_5") (pintype "passive"))
    )
    (net (code "71") (name "/RS232_R") (class "Default")
      (node (ref "J7") (pin "3") (pinfunction "3_3") (pintype "passive"))
      (node (ref "U5") (pin "8") (pinfunction "RIN2_8") (pintype "passive"))
    )
    (net (code "72") (name "/RS232_T") (class "Default")
      (node (ref "J7") (pin "1") (pinfunction "1_1") (pintype "passive"))
      (node (ref "U5") (pin "7") (pinfunction "DOUT2_7") (pintype "passive"))
    )
    (net (code "73") (name "/SD_CS") (class "Default")
      (node (ref "J8") (pin "22") (pinfunction "SD_CS_22") (pintype "passive"))
      (node (ref "U7") (pin "29") (pinfunction "PA4_29") (pintype "passive"))
    )
    (net (code "74") (name "/SPI_CLK") (class "Default")
      (node (ref "J8") (pin "34") (pinfunction "SPI_CLK_34") (pintype "passive"))
      (node (ref "U7") (pin "30") (pinfunction "PA5_30") (pintype "passive"))
    )
    (net (code "75") (name "/SPI_MISO") (class "Default")
      (node (ref "J8") (pin "29") (pinfunction "SPI_MISO_29") (pintype "passive"))
      (node (ref "U7") (pin "31") (pinfunction "PA6_31") (pintype "passive"))
    )
    (net (code "76") (name "/SPI_MOSI") (class "Default")
      (node (ref "J8") (pin "30") (pinfunction "SPI_MOSI_30") (pintype "passive"))
      (node (ref "U7") (pin "32") (pinfunction "PA7_32") (pintype "passive"))
    )
    (net (code "77") (name "/SWCLK") (class "Default")
      (node (ref "J4") (pin "1") (pinfunction "1_1") (pintype "passive"))
      (node (ref "U7") (pin "76") (pinfunction "PA14_76") (pintype "passive"))
    )
    (net (code "78") (name "/SWDIO") (class "Default")
      (node (ref "J4") (pin "3") (pinfunction "3_3") (pintype "passive"))
      (node (ref "U7") (pin "72") (pinfunction "PA13_72") (pintype "passive"))
    )
    (net (code "79") (name "/T_CS") (class "Default")
      (node (ref "J8") (pin "33") (pinfunction "T_CS_33") (pintype "passive"))
      (node (ref "U7") (pin "66") (pinfunction "PC9_66") (pintype "passive"))
    )
    (net (code "80") (name "/T_PEN") (class "Default")
      (node (ref "J8") (pin "31") (pinfunction "T_PEN_31") (pintype "passive"))
      (node (ref "U7") (pin "65") (pinfunction "PC8_65") (pintype "passive"))
    )
    (net (code "81") (name "/USART1_RX") (class "Default")
      (node (ref "U5") (pin "9") (pinfunction "ROUT2_9") (pintype "passive"))
      (node (ref "U7") (pin "69") (pinfunction "PA10_69") (pintype "passive"))
    )
    (net (code "82") (name "/USART1_TX") (class "Default")
      (node (ref "U5") (pin "10") (pinfunction "DIN2_10") (pintype "passive"))
      (node (ref "U7") (pin "68") (pinfunction "PA9_68") (pintype "passive"))
    )
    (net (code "83") (name "/USART2_RX") (class "Default")
      (node (ref "R17") (pin "2") (pinfunction "2_2") (pintype "passive"))
      (node (ref "U7") (pin "26") (pinfunction "PA3_26") (pintype "passive"))
    )
    (net (code "84") (name "/USART2_TX") (class "Default")
      (node (ref "R21") (pin "2") (pinfunction "2_2") (pintype "passive"))
      (node (ref "U7") (pin "25") (pinfunction "PA2_25") (pintype "passive"))
    )
    (net (code "85") (name "/USART3_RX") (class "Default")
      (node (ref "R19") (pin "2") (pinfunction "2_2") (pintype "passive"))
      (node (ref "U7") (pin "48") (pinfunction "PB11_48") (pintype "passive"))
    )
    (net (code "86") (name "/USART3_TX") (class "Default")
      (node (ref "R18") (pin "2") (pinfunction "2_2") (pintype "passive"))
      (node (ref "U7") (pin "47") (pinfunction "PB10_47") (pintype "passive"))
    )
    (net (code "87") (name "/Vref_3V") (class "Default")
      (node (ref "D3") (pin "2") (pinfunction "2_2") (pintype "passive"))
      (node (ref "R11") (pin "1") (pinfunction "1_1") (pintype "passive"))
      (node (ref "R12") (pin "1") (pinfunction "1_1") (pintype "passive"))
      (node (ref "R14") (pin "2") (pinfunction "2_2") (pintype "passive"))
      (node (ref "U7") (pin "21") (pinfunction "VREF+_21") (pintype "passive"))
    )
    (net (code "88") (name "3.3V") (class "Default")
      (node (ref "C11") (pin "2") (pinfunction "2_2") (pintype "passive"))
      (node (ref "C23") (pin "1") (pinfunction "1_1") (pintype "passive"))
      (node (ref "C24") (pin "2") (pinfunction "2_2") (pintype "passive"))
      (node (ref "C26") (pin "2") (pinfunction "2_2") (pintype "passive"))
      (node (ref "C27") (pin "2") (pinfunction "2_2") (pintype "passive"))
      (node (ref "C28") (pin "2") (pinfunction "2_2") (pintype "passive"))
      (node (ref "C29") (pin "2") (pinfunction "2_2") (pintype "passive"))
      (node (ref "C30") (pin "2") (pinfunction "2_2") (pintype "passive"))
      (node (ref "C31") (pin "2") (pinfunction "2_2") (pintype "passive"))
      (node (ref "C32") (pin "2") (pinfunction "2_2") (pintype "passive"))
      (node (ref "C35") (pin "2") (pinfunction "2_2") (pintype "passive"))
      (node (ref "C36") (pin "2") (pinfunction "2_2") (pintype "passive"))
      (node (ref "C37") (pin "2") (pinfunction "2_2") (pintype "passive"))
      (node (ref "D2") (pin "2") (pinfunction "K_2") (pintype "passive"))
      (node (ref "J6") (pin "1") (pinfunction "1_1") (pintype "passive"))
      (node (ref "P1") (pin "1") (pinfunction "1_1") (pintype "passive"))
      (node (ref "P1") (pin "37") (pinfunction "37_37") (pintype "passive"))
      (node (ref "P1") (pin "39") (pinfunction "39_39") (pintype "passive"))
      (node (ref "R11") (pin "2") (pinfunction "2_2") (pintype "passive"))
      (node (ref "R22") (pin "2") (pinfunction "2_2") (pintype "passive"))
      (node (ref "R24") (pin "1") (pinfunction "1_1") (pintype "passive"))
      (node (ref "R27") (pin "2") (pinfunction "2_2") (pintype "passive"))
      (node (ref "U1") (pin "5") (pinfunction "VOUT_5") (pintype "passive"))
      (node (ref "U5") (pin "16") (pinfunction "VCC_16") (pintype "passive"))
      (node (ref "U7") (pin "100") (pinfunction "VDD_100") (pintype "passive"))
      (node (ref "U7") (pin "11") (pinfunction "VDD_11") (pintype "passive"))
      (node (ref "U7") (pin "19") (pinfunction "VDD_19") (pintype "passive"))
      (node (ref "U7") (pin "22") (pinfunction "VDDA_22") (pintype "passive"))
      (node (ref "U7") (pin "28") (pinfunction "VDD_28") (pintype "passive"))
      (node (ref "U7") (pin "50") (pinfunction "VDD_50") (pintype "passive"))
      (node (ref "U7") (pin "6") (pinfunction "VBAT_6") (pintype "passive"))
      (node (ref "U7") (pin "75") (pinfunction "VDD_75") (pintype "passive"))
    )
    (net (code "89") (name "5V") (class "Default")
      (node (ref "C13") (pin "2") (pinfunction "2_2") (pintype "passive"))
      (node (ref "C15") (pin "2") (pinfunction "2_2") (pintype "passive"))
      (node (ref "C40") (pin "2") (pinfunction "2_2") (pintype "passive"))
      (node (ref "C41") (pin "2") (pinfunction "2_2") (pintype "passive"))
      (node (ref "D6") (pin "2") (pinfunction "K_2") (pintype "passive"))
      (node (ref "J8") (pin "24") (pinfunction "VCC_24") (pintype "passive"))
      (node (ref "J8") (pin "25") (pinfunction "VCC_25") (pintype "passive"))
      (node (ref "L1") (pin "1") (pinfunction "1_1") (pintype "passive"))
      (node (ref "L3") (pin "2") (pinfunction "2_2") (pintype "passive"))
      (node (ref "P1") (pin "41") (pinfunction "41_41") (pintype "passive"))
      (node (ref "P1") (pin "43") (pinfunction "43_43") (pintype "passive"))
      (node (ref "R10") (pin "2") (pinfunction "2_2") (pintype "passive"))
    )
    (net (code "90") (name "12V") (class "Default")
      (node (ref "C12") (pin "2") (pinfunction "2_2") (pintype "passive"))
      (node (ref "C14") (pin "2") (pinfunction "2_2") (pintype "passive"))
      (node (ref "J2") (pin "1") (pinfunction "1_1") (pintype "passive"))
      (node (ref "L2") (pin "2") (pinfunction "2_2") (pintype "passive"))
      (node (ref "R9") (pin "2") (pinfunction "2_2") (pintype "passive"))
    )
    (net (code "91") (name "24V") (class "Default")
      (node (ref "C1") (pin "2") (pinfunction "2_2") (pintype "passive"))
      (node (ref "C2") (pin "2") (pinfunction "2_2") (pintype "passive"))
      (node (ref "D1") (pin "2") (pinfunction "K_2") (pintype "passive"))
      (node (ref "R1") (pin "2") (pinfunction "2_2") (pintype "passive"))
      (node (ref "R2") (pin "2") (pinfunction "2_2") (pintype "passive"))
      (node (ref "R3") (pin "2") (pinfunction "2_2") (pintype "passive"))
      (node (ref "U2") (pin "2") (pinfunction "IN_2") (pintype "passive"))
      (node (ref "U3") (pin "2") (pinfunction "IN_2") (pintype "passive"))
    )
    (net (code "92") (name "GND") (class "Default")
      (node (ref "C1") (pin "1") (pinfunction "1_1") (pintype "passive"))
      (node (ref "C10") (pin "1") (pinfunction "1_1") (pintype "passive"))
      (node (ref "C11") (pin "1") (pinfunction "1_1") (pintype "passive"))
      (node (ref "C12") (pin "1") (pinfunction "1_1") (pintype "passive"))
      (node (ref "C13") (pin "1") (pinfunction "1_1") (pintype "passive"))
      (node (ref "C14") (pin "1") (pinfunction "1_1") (pintype "passive"))
      (node (ref "C15") (pin "1") (pinfunction "1_1") (pintype "passive"))
      (node (ref "C16") (pin "1") (pinfunction "1_1") (pintype "passive"))
      (node (ref "C18") (pin "1") (pinfunction "1_1") (pintype "passive"))
      (node (ref "C19") (pin "1") (pinfunction "1_1") (pintype "passive"))
      (node (ref "C2") (pin "1") (pinfunction "1_1") (pintype "passive"))
      (node (ref "C21") (pin "1") (pinfunction "1_1") (pintype "passive"))
      (node (ref "C22") (pin "1") (pinfunction "1_1") (pintype "passive"))
      (node (ref "C23") (pin "2") (pinfunction "2_2") (pintype "passive"))
      (node (ref "C24") (pin "1") (pinfunction "1_1") (pintype "passive"))
      (node (ref "C25") (pin "1") (pinfunction "1_1") (pintype "passive"))
      (node (ref "C26") (pin "1") (pinfunction "1_1") (pintype "passive"))
      (node (ref "C27") (pin "1") (pinfunction "1_1") (pintype "passive"))
      (node (ref "C28") (pin "1") (pinfunction "1_1") (pintype "passive"))
      (node (ref "C29") (pin "1") (pinfunction "1_1") (pintype "passive"))
      (node (ref "C3") (pin "1") (pinfunction "1_1") (pintype "passive"))
      (node (ref "C30") (pin "1") (pinfunction "1_1") (pintype "passive"))
      (node (ref "C31") (pin "1") (pinfunction "1_1") (pintype "passive"))
      (node (ref "C32") (pin "1") (pinfunction "1_1") (pintype "passive"))
      (node (ref "C33") (pin "2") (pinfunction "2_2") (pintype "passive"))
      (node (ref "C34") (pin "2") (pinfunction "2_2") (pintype "passive"))
      (node (ref "C35") (pin "1") (pinfunction "1_1") (pintype "passive"))
      (node (ref "C36") (pin "1") (pinfunction "1_1") (pintype "passive"))
      (node (ref "C37") (pin "1") (pinfunction "1_1") (pintype "passive"))
      (node (ref "C38") (pin "1") (pinfunction "1_1") (pintype "passive"))
      (node (ref "C39") (pin "2") (pinfunction "2_2") (pintype "passive"))
      (node (ref "C4") (pin "1") (pinfunction "1_1") (pintype "passive"))
      (node (ref "C40") (pin "1") (pinfunction "1_1") (pintype "passive"))
      (node (ref "C41") (pin "1") (pinfunction "1_1") (pintype "passive"))
      (node (ref "C5") (pin "1") (pinfunction "1_1") (pintype "passive"))
      (node (ref "D3") (pin "3") (pinfunction "3_3") (pintype "passive"))
      (node (ref "D4") (pin "2") (pinfunction "K_2") (pintype "passive"))
      (node (ref "D5") (pin "2") (pinfunction "K_2") (pintype "passive"))
      (node (ref "J1") (pin "2") (pinfunction "-_2") (pintype "passive"))
      (node (ref "J1") (pin "3") (pinfunction "-_3") (pintype "passive"))
      (node (ref "J2") (pin "2") (pinfunction "2_2") (pintype "passive"))
      (node (ref "J2") (pin "3") (pinfunction "3_3") (pintype "passive"))
      (node (ref "J2") (pin "4") (pinfunction "4_4") (pintype "passive"))
      (node (ref "J3") (pin "5") (pinfunction "GND_5") (pintype "passive"))
      (node (ref "J3") (pin "6") (pinfunction "SHELL_6") (pintype "passive"))
      (node (ref "J3") (pin "7") (pinfunction "SHELL_7") (pintype "passive"))
      (node (ref "J3") (pin "8") (pinfunction "SHELL_8") (pintype "passive"))
      (node (ref "J3") (pin "9") (pinfunction "SHELL_9") (pintype "passive"))
      (node (ref "J4") (pin "2") (pinfunction "2_2") (pintype "passive"))
      (node (ref "J5") (pin "2") (pinfunction "2_2") (pintype "passive"))
      (node (ref "J5") (pin "4") (pinfunction "4_4") (pintype "passive"))
      (node (ref "J5") (pin "5") (pinfunction "5_5") (pintype "passive"))
      (node (ref "J5") (pin "6") (pinfunction "6_6") (pintype "passive"))
      (node (ref "J6") (pin "4") (pinfunction "4_4") (pintype "passive"))
      (node (ref "J6") (pin "5") (pinfunction "5_5") (pintype "passive"))
      (node (ref "J6") (pin "6") (pinfunction "6_6") (pintype "passive"))
      (node (ref "J7") (pin "2") (pinfunction "2_2") (pintype "passive"))
      (node (ref "J7") (pin "4") (pinfunction "4_4") (pintype "passive"))
      (node (ref "J7") (pin "5") (pinfunction "5_5") (pintype "passive"))
      (node (ref "J8") (pin "26") (pinfunction "GND_26") (pintype "passive"))
      (node (ref "P1") (pin "2") (pinfunction "2_2") (pintype "passive"))
      (node (ref "P1") (pin "38") (pinfunction "38_38") (pintype "passive"))
      (node (ref "P1") (pin "40") (pinfunction "40_40") (pintype "passive"))
      (node (ref "P1") (pin "42") (pinfunction "42_42") (pintype "passive"))
      (node (ref "P1") (pin "44") (pinfunction "44_44") (pintype "passive"))
      (node (ref "R13") (pin "2") (pinfunction "2_2") (pintype "passive"))
      (node (ref "R23") (pin "1") (pinfunction "1_1") (pintype "passive"))
      (node (ref "R28") (pin "1") (pinfunction "1_1") (pintype "passive"))
      (node (ref "R4") (pin "1") (pinfunction "1_1") (pintype "passive"))
      (node (ref "R5") (pin "2") (pinfunction "2_2") (pintype "passive"))
      (node (ref "R6") (pin "2") (pinfunction "2_2") (pintype "passive"))
      (node (ref "R7") (pin "1") (pinfunction "1_1") (pintype "passive"))
      (node (ref "R8") (pin "1") (pinfunction "1_1") (pintype "passive"))
      (node (ref "U1") (pin "2") (pinfunction "GND_2") (pintype "passive"))
      (node (ref "U2") (pin "4") (pinfunction "GND_4") (pintype "passive"))
      (node (ref "U2") (pin "9") (pinfunction "PAD_9") (pintype "passive"))
      (node (ref "U3") (pin "4") (pinfunction "GND_4") (pintype "passive"))
      (node (ref "U3") (pin "9") (pinfunction "PAD_9") (pintype "passive"))
      (node (ref "U4") (pin "2") (pinfunction "GND_2") (pintype "passive"))
      (node (ref "U5") (pin "15") (pinfunction "GND_15") (pintype "passive"))
      (node (ref "U6") (pin "2") (pinfunction "GND_2") (pintype "passive"))
      (node (ref "U6") (pin "25") (pinfunction "PAD_25") (pintype "passive"))
      (node (ref "U7") (pin "10") (pinfunction "VSS_10") (pintype "passive"))
      (node (ref "U7") (pin "20") (pinfunction "VSSA_20") (pintype "passive"))
      (node (ref "U7") (pin "27") (pinfunction "VSS_27") (pintype "passive"))
      (node (ref "U7") (pin "74") (pinfunction "VSS_74") (pintype "passive"))
    )
    (net (code "93") (name "Net-(C6-Pad1)") (class "Default")
      (node (ref "C6") (pin "1") (pinfunction "1_1") (pintype "passive"))
      (node (ref "R5") (pin "1") (pinfunction "1_1") (pintype "passive"))
    )
    (net (code "94") (name "Net-(C7-Pad1)") (class "Default")
      (node (ref "C7") (pin "1") (pinfunction "1_1") (pintype "passive"))
      (node (ref "R6") (pin "1") (pinfunction "1_1") (pintype "passive"))
    )
    (net (code "95") (name "Net-(D1-A)") (class "Default")
      (node (ref "D1") (pin "1") (pinfunction "A_1") (pintype "passive"))
      (node (ref "J1") (pin "1") (pinfunction "+_1") (pintype "passive"))
    )
    (net (code "96") (name "Net-(D3-Pad1)") (class "Default")
      (node (ref "D3") (pin "1") (pinfunction "1_1") (pintype "passive"))
      (node (ref "R12") (pin "2") (pinfunction "2_2") (pintype "passive"))
      (node (ref "R13") (pin "1") (pinfunction "1_1") (pintype "passive"))
    )
    (net (code "97") (name "Net-(D4-A)") (class "Default")
      (node (ref "D4") (pin "1") (pinfunction "A_1") (pintype "passive"))
      (node (ref "R25") (pin "2") (pinfunction "2_2") (pintype "passive"))
    )
    (net (code "98") (name "Net-(D5-A)") (class "Default")
      (node (ref "D5") (pin "1") (pinfunction "A_1") (pintype "passive"))
      (node (ref "R26") (pin "2") (pinfunction "2_2") (pintype "passive"))
    )
    (net (code "99") (name "Net-(J3-D+)") (class "Default")
      (node (ref "J3") (pin "3") (pinfunction "D+_3") (pintype "passive"))
      (node (ref "R16") (pin "1") (pinfunction "1_1") (pintype "passive"))
      (node (ref "U4") (pin "1") (pinfunction "D1_1") (pintype "passive"))
    )
    (net (code "100") (name "Net-(J3-D-)") (class "Default")
      (node (ref "J3") (pin "2") (pinfunction "D-_2") (pintype "passive"))
      (node (ref "R15") (pin "1") (pinfunction "1_1") (pintype "passive"))
      (node (ref "U4") (pin "3") (pinfunction "D2_3") (pintype "passive"))
    )
    (net (code "101") (name "Net-(R3-Pad1)") (class "Default")
      (node (ref "R3") (pin "1") (pinfunction "1_1") (pintype "passive"))
      (node (ref "R30") (pin "1") (pinfunction "1_1") (pintype "passive"))
      (node (ref "R4") (pin "2") (pinfunction "2_2") (pintype "passive"))
    )
    (net (code "102") (name "Net-(U1-BYP{slash}ADJ)") (class "Default")
      (node (ref "C10") (pin "2") (pinfunction "2_2") (pintype "passive"))
      (node (ref "U1") (pin "4") (pinfunction "BYP/ADJ_4") (pintype "passive"))
    )
    (net (code "103") (name "Net-(U1-EN)") (class "Default")
      (node (ref "C5") (pin "2") (pinfunction "2_2") (pintype "passive"))
      (node (ref "L1") (pin "2") (pinfunction "2_2") (pintype "passive"))
      (node (ref "U1") (pin "1") (pinfunction "VIN_1") (pintype "passive"))
      (node (ref "U1") (pin "3") (pinfunction "EN_3") (pintype "passive"))
    )
    (net (code "104") (name "Net-(U2-BS)") (class "Default")
      (node (ref "C8") (pin "1") (pinfunction "1_1") (pintype "passive"))
      (node (ref "U2") (pin "1") (pinfunction "BS_1") (pintype "passive"))
    )
    (net (code "105") (name "Net-(U2-COMP)") (class "Default")
      (node (ref "C6") (pin "2") (pinfunction "2_2") (pintype "passive"))
      (node (ref "U2") (pin "6") (pinfunction "COMP_6") (pintype "passive"))
    )
    (net (code "106") (name "Net-(U2-EN)") (class "Default")
      (node (ref "R1") (pin "1") (pinfunction "1_1") (pintype "passive"))
      (node (ref "U2") (pin "7") (pinfunction "EN_7") (pintype "passive"))
    )
    (net (code "107") (name "Net-(U2-FB)") (class "Default")
      (node (ref "R7") (pin "2") (pinfunction "2_2") (pintype "passive"))
      (node (ref "R9") (pin "1") (pinfunction "1_1") (pintype "passive"))
      (node (ref "U2") (pin "5") (pinfunction "FB_5") (pintype "passive"))
    )
    (net (code "108") (name "Net-(U2-SS)") (class "Default")
      (node (ref "C3") (pin "2") (pinfunction "2_2") (pintype "passive"))
      (node (ref "U2") (pin "8") (pinfunction "SS_8") (pintype "passive"))
    )
    (net (code "109") (name "Net-(U2-SW)") (class "Default")
      (node (ref "C8") (pin "2") (pinfunction "2_2") (pintype "passive"))
      (node (ref "L2") (pin "1") (pinfunction "1_1") (pintype "passive"))
      (node (ref "U2") (pin "3") (pinfunction "SW_3") (pintype "passive"))
    )
    (net (code "110") (name "Net-(U3-BS)") (class "Default")
      (node (ref "C9") (pin "1") (pinfunction "1_1") (pintype "passive"))
      (node (ref "U3") (pin "1") (pinfunction "BS_1") (pintype "passive"))
    )
    (net (code "111") (name "Net-(U3-COMP)") (class "Default")
      (node (ref "C7") (pin "2") (pinfunction "2_2") (pintype "passive"))
      (node (ref "U3") (pin "6") (pinfunction "COMP_6") (pintype "passive"))
    )
    (net (code "112") (name "Net-(U3-EN)") (class "Default")
      (node (ref "R2") (pin "1") (pinfunction "1_1") (pintype "passive"))
      (node (ref "U3") (pin "7") (pinfunction "EN_7") (pintype "passive"))
    )
    (net (code "113") (name "Net-(U3-FB)") (class "Default")
      (node (ref "R10") (pin "1") (pinfunction "1_1") (pintype "passive"))
      (node (ref "R8") (pin "2") (pinfunction "2_2") (pintype "passive"))
      (node (ref "U3") (pin "5") (pinfunction "FB_5") (pintype "passive"))
    )
    (net (code "114") (name "Net-(U3-SS)") (class "Default")
      (node (ref "C4") (pin "2") (pinfunction "2_2") (pintype "passive"))
      (node (ref "U3") (pin "8") (pinfunction "SS_8") (pintype "passive"))
    )
    (net (code "115") (name "Net-(U3-SW)") (class "Default")
      (node (ref "C9") (pin "2") (pinfunction "2_2") (pintype "passive"))
      (node (ref "L3") (pin "1") (pinfunction "1_1") (pintype "passive"))
      (node (ref "U3") (pin "3") (pinfunction "SW_3") (pintype "passive"))
    )
    (net (code "116") (name "Net-(U5-C1+)") (class "Default")
      (node (ref "C17") (pin "1") (pinfunction "1_1") (pintype "passive"))
      (node (ref "U5") (pin "1") (pinfunction "C1+_1") (pintype "passive"))
    )
    (net (code "117") (name "Net-(U5-C1-)") (class "Default")
      (node (ref "C17") (pin "2") (pinfunction "2_2") (pintype "passive"))
      (node (ref "U5") (pin "3") (pinfunction "C1-_3") (pintype "passive"))
    )
    (net (code "118") (name "Net-(U5-C2+)") (class "Default")
      (node (ref "C20") (pin "1") (pinfunction "1_1") (pintype "passive"))
      (node (ref "U5") (pin "4") (pinfunction "C2+_4") (pintype "passive"))
    )
    (net (code "119") (name "Net-(U5-C2-)") (class "Default")
      (node (ref "C20") (pin "2") (pinfunction "2_2") (pintype "passive"))
      (node (ref "U5") (pin "5") (pinfunction "C2-_5") (pintype "passive"))
    )
    (net (code "120") (name "Net-(U5-V+)") (class "Default")
      (node (ref "C18") (pin "2") (pinfunction "2_2") (pintype "passive"))
      (node (ref "U5") (pin "2") (pinfunction "V+_2") (pintype "passive"))
    )
    (net (code "121") (name "Net-(U5-V-)") (class "Default")
      (node (ref "C19") (pin "2") (pinfunction "2_2") (pintype "passive"))
      (node (ref "U5") (pin "6") (pinfunction "V-_6") (pintype "passive"))
    )
    (net (code "122") (name "Net-(U6-D+)") (class "Default")
      (node (ref "R16") (pin "2") (pinfunction "2_2") (pintype "passive"))
      (node (ref "U6") (pin "3") (pinfunction "D+_3") (pintype "passive"))
    )
    (net (code "123") (name "Net-(U6-D-)") (class "Default")
      (node (ref "R15") (pin "2") (pinfunction "2_2") (pintype "passive"))
      (node (ref "U6") (pin "4") (pinfunction "D-_4") (pintype "passive"))
    )
    (net (code "124") (name "Net-(U6-RXD_ECI)") (class "Default")
      (node (ref "R21") (pin "1") (pinfunction "1_1") (pintype "passive"))
      (node (ref "U6") (pin "12") (pinfunction "RXD_ECI_12") (pintype "passive"))
    )
    (net (code "125") (name "Net-(U6-RXD_SCI)") (class "Default")
      (node (ref "R18") (pin "1") (pinfunction "1_1") (pintype "passive"))
      (node (ref "U6") (pin "20") (pinfunction "RXD_SCI_20") (pintype "passive"))
    )
    (net (code "126") (name "Net-(U6-TXD_ECI)") (class "Default")
      (node (ref "R17") (pin "1") (pinfunction "1_1") (pintype "passive"))
      (node (ref "U6") (pin "13") (pinfunction "TXD_ECI_13") (pintype "passive"))
    )
    (net (code "127") (name "Net-(U6-TXD_SCI)") (class "Default")
      (node (ref "R19") (pin "1") (pinfunction "1_1") (pintype "passive"))
      (node (ref "U6") (pin "21") (pinfunction "TXD_SCI_21") (pintype "passive"))
    )
    (net (code "128") (name "Net-(U6-VDD)") (class "Default")
      (node (ref "C16") (pin "2") (pinfunction "2_2") (pintype "passive"))
      (node (ref "C21") (pin "2") (pinfunction "2_2") (pintype "passive"))
      (node (ref "R20") (pin "2") (pinfunction "2_2") (pintype "passive"))
      (node (ref "U6") (pin "5") (pinfunction "VIO_5") (pintype "passive"))
      (node (ref "U6") (pin "6") (pinfunction "VDD_6") (pintype "passive"))
    )
    (net (code "129") (name "Net-(U6-~{RST})") (class "Default")
      (node (ref "R20") (pin "1") (pinfunction "1_1") (pintype "passive"))
      (node (ref "U6") (pin "9") (pinfunction "~{RST}_9") (pintype "passive"))
    )
    (net (code "130") (name "Net-(U7-VCAP_1)") (class "Default")
      (node (ref "C38") (pin "2") (pinfunction "2_2") (pintype "passive"))
      (node (ref "U7") (pin "49") (pinfunction "VCAP_1_49") (pintype "passive"))
    )
    (net (code "131") (name "Net-(U7-VCAP_2)") (class "Default")
      (node (ref "C39") (pin "1") (pinfunction "1_1") (pintype "passive"))
      (node (ref "U7") (pin "73") (pinfunction "VCAP_2_73") (pintype "passive"))
    )
    (net (code "132") (name "Net-(X1-OSC1)") (class "Default")
      (node (ref "C33") (pin "1") (pinfunction "1_1") (pintype "passive"))
      (node (ref "R29") (pin "2") (pinfunction "2_2") (pintype "passive"))
      (node (ref "X1") (pin "1") (pinfunction "OSC1_1") (pintype "passive"))
    )
    (net (code "133") (name "VBUS") (class "Default")
      (node (ref "C22") (pin "2") (pinfunction "2_2") (pintype "passive"))
      (node (ref "D6") (pin "1") (pinfunction "A_1") (pintype "passive"))
      (node (ref "J3") (pin "1") (pinfunction "VBUS_1") (pintype "passive"))
      (node (ref "U4") (pin "5") (pinfunction "VCC_5") (pintype "passive"))
      (node (ref "U6") (pin "7") (pinfunction "REGIN_7") (pintype "passive"))
      (node (ref "U6") (pin "8") (pinfunction "VBUS_8") (pintype "passive"))
    )
    (net (code "134") (name "unconnected-(J3-ID-Pad4)") (class "Default")
      (node (ref "J3") (pin "4") (pinfunction "ID_4") (pintype "passive"))
    )
    (net (code "135") (name "unconnected-(J8-NC-Pad27)") (class "Default")
      (node (ref "J8") (pin "27") (pinfunction "NC_27") (pintype "passive"))
    )
    (net (code "136") (name "unconnected-(J8-NC-Pad28)") (class "Default")
      (node (ref "J8") (pin "28") (pinfunction "NC_28") (pintype "passive"))
    )
    (net (code "137") (name "unconnected-(U4-D3-Pad4)") (class "Default")
      (node (ref "U4") (pin "4") (pinfunction "D3_4") (pintype "passive"))
    )
    (net (code "138") (name "unconnected-(U4-D4-Pad6)") (class "Default")
      (node (ref "U4") (pin "6") (pinfunction "D4_6") (pintype "passive"))
    )
    (net (code "139") (name "unconnected-(U5-DIN1-Pad11)") (class "Default")
      (node (ref "U5") (pin "11") (pinfunction "DIN1_11") (pintype "passive"))
    )
    (net (code "140") (name "unconnected-(U5-DOUT1-Pad14)") (class "Default")
      (node (ref "U5") (pin "14") (pinfunction "DOUT1_14") (pintype "passive"))
    )
    (net (code "141") (name "unconnected-(U5-RIN1-Pad13)") (class "Default")
      (node (ref "U5") (pin "13") (pinfunction "RIN1_13") (pintype "passive"))
    )
    (net (code "142") (name "unconnected-(U5-ROUT1-Pad12)") (class "Default")
      (node (ref "U5") (pin "12") (pinfunction "ROUT1_12") (pintype "passive"))
    )
    (net (code "143") (name "unconnected-(U6-CTS_ECI-Pad10)") (class "Default")
      (node (ref "U6") (pin "10") (pinfunction "CTS_ECI_10") (pintype "passive"))
    )
    (net (code "144") (name "unconnected-(U6-CTS_SCI-Pad18)") (class "Default")
      (node (ref "U6") (pin "18") (pinfunction "CTS_SCI_18") (pintype "passive"))
    )
    (net (code "145") (name "unconnected-(U6-GPIO.0_ECI{slash}DTR_ECI-Pad15)") (class "Default")
      (node (ref "U6") (pin "15") (pinfunction "GPIO.0_ECI/DTR_ECI_15") (pintype "passive"))
    )
    (net (code "146") (name "unconnected-(U6-GPIO.0_SCI{slash}DCD_SCI-Pad24)") (class "Default")
      (node (ref "U6") (pin "24") (pinfunction "GPIO.0_SCI/DCD_SCI_24") (pintype "passive"))
    )
    (net (code "147") (name "unconnected-(U6-GPIO.1_ECI{slash}DSR_ECI-Pad14)") (class "Default")
      (node (ref "U6") (pin "14") (pinfunction "GPIO.1_ECI/DSR_ECI_14") (pintype "passive"))
    )
    (net (code "148") (name "unconnected-(U6-GPIO.1_SCI{slash}DTR_SCI-Pad23)") (class "Default")
      (node (ref "U6") (pin "23") (pinfunction "GPIO.1_SCI/DTR_SCI_23") (pintype "passive"))
    )
    (net (code "149") (name "unconnected-(U6-GPIO.2_SCI{slash}DSR_SCI-Pad22)") (class "Default")
      (node (ref "U6") (pin "22") (pinfunction "GPIO.2_SCI/DSR_SCI_22") (pintype "passive"))
    )
    (net (code "150") (name "unconnected-(U6-NC{slash}DCD_ECI{slash}VPP-Pad16)") (class "Default")
      (node (ref "U6") (pin "16") (pinfunction "NC/DCD_ECI/VPP_16") (pintype "passive"))
    )
    (net (code "151") (name "unconnected-(U6-RTS_ECI-Pad11)") (class "Default")
      (node (ref "U6") (pin "11") (pinfunction "RTS_ECI_11") (pintype "passive"))
    )
    (net (code "152") (name "unconnected-(U6-RTS_SCI-Pad19)") (class "Default")
      (node (ref "U6") (pin "19") (pinfunction "RTS_SCI_19") (pintype "passive"))
    )
    (net (code "153") (name "unconnected-(U6-~{SUSPEND}{slash}RI_ECI-Pad17)") (class "Default")
      (node (ref "U6") (pin "17") (pinfunction "~{SUSPEND}/RI_ECI_17") (pintype "passive"))
    )
    (net (code "154") (name "unconnected-(U6-~{SUSPEND}{slash}RI_SCI-Pad1)") (class "Default")
      (node (ref "U6") (pin "1") (pinfunction "~{SUSPEND}/RI_SCI_1") (pintype "passive"))
    )
    (net (code "155") (name "unconnected-(U7-RFU-Pad99)") (class "Default")
      (node (ref "U7") (pin "99") (pinfunction "RFU_99") (pintype "passive"))
    )
  )
)
